# OpenMyxa.net
KiCad netlist of a schematic drawn in EAGLE
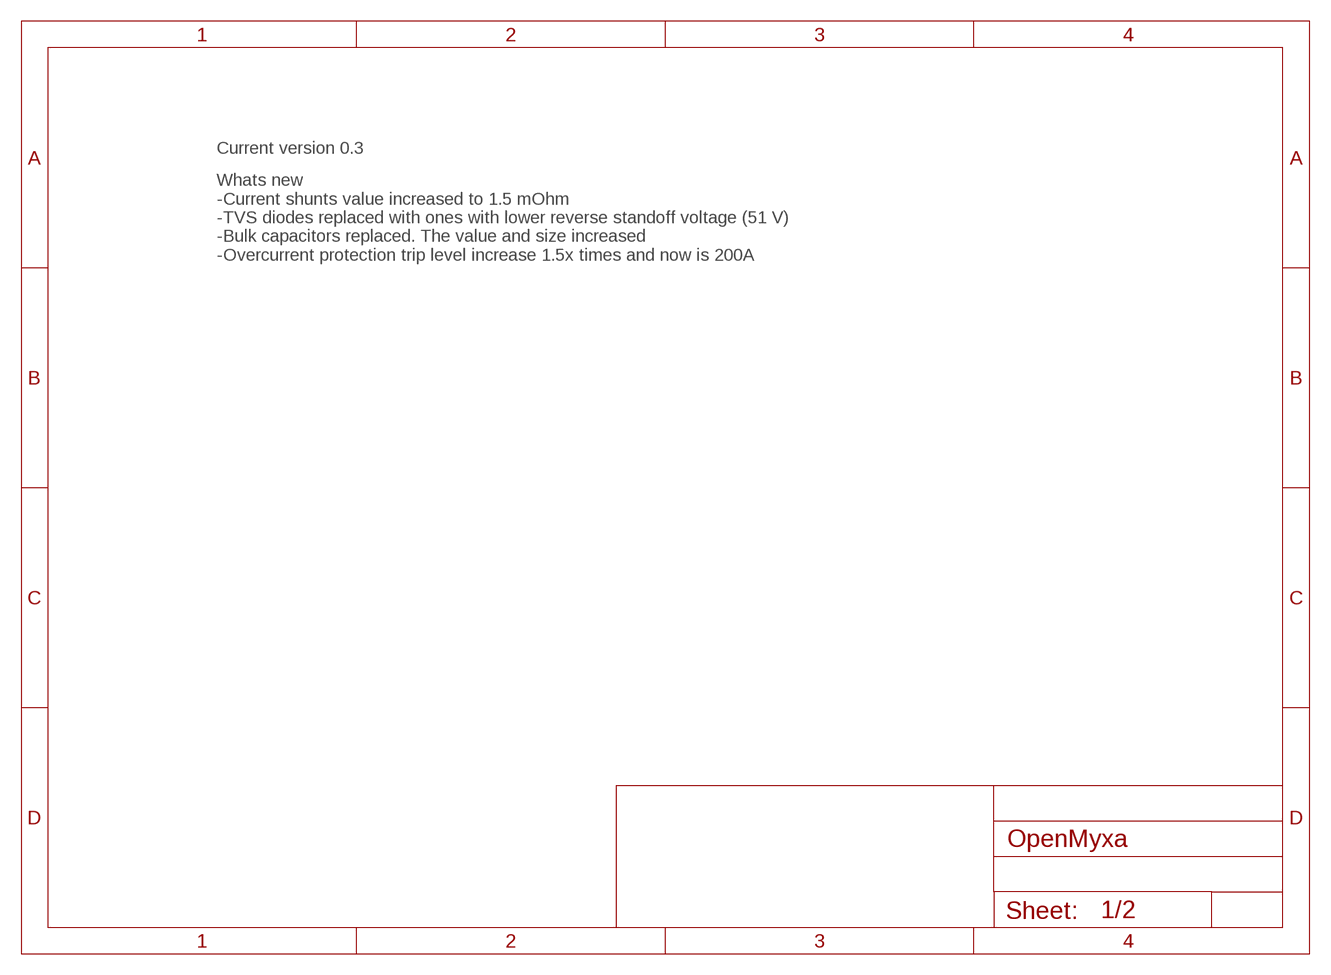
[diagram p0: schematic, sheet 1]
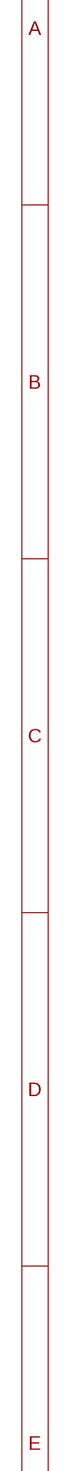
[diagram p1: schematic, sheet 2, part 1 of 2]
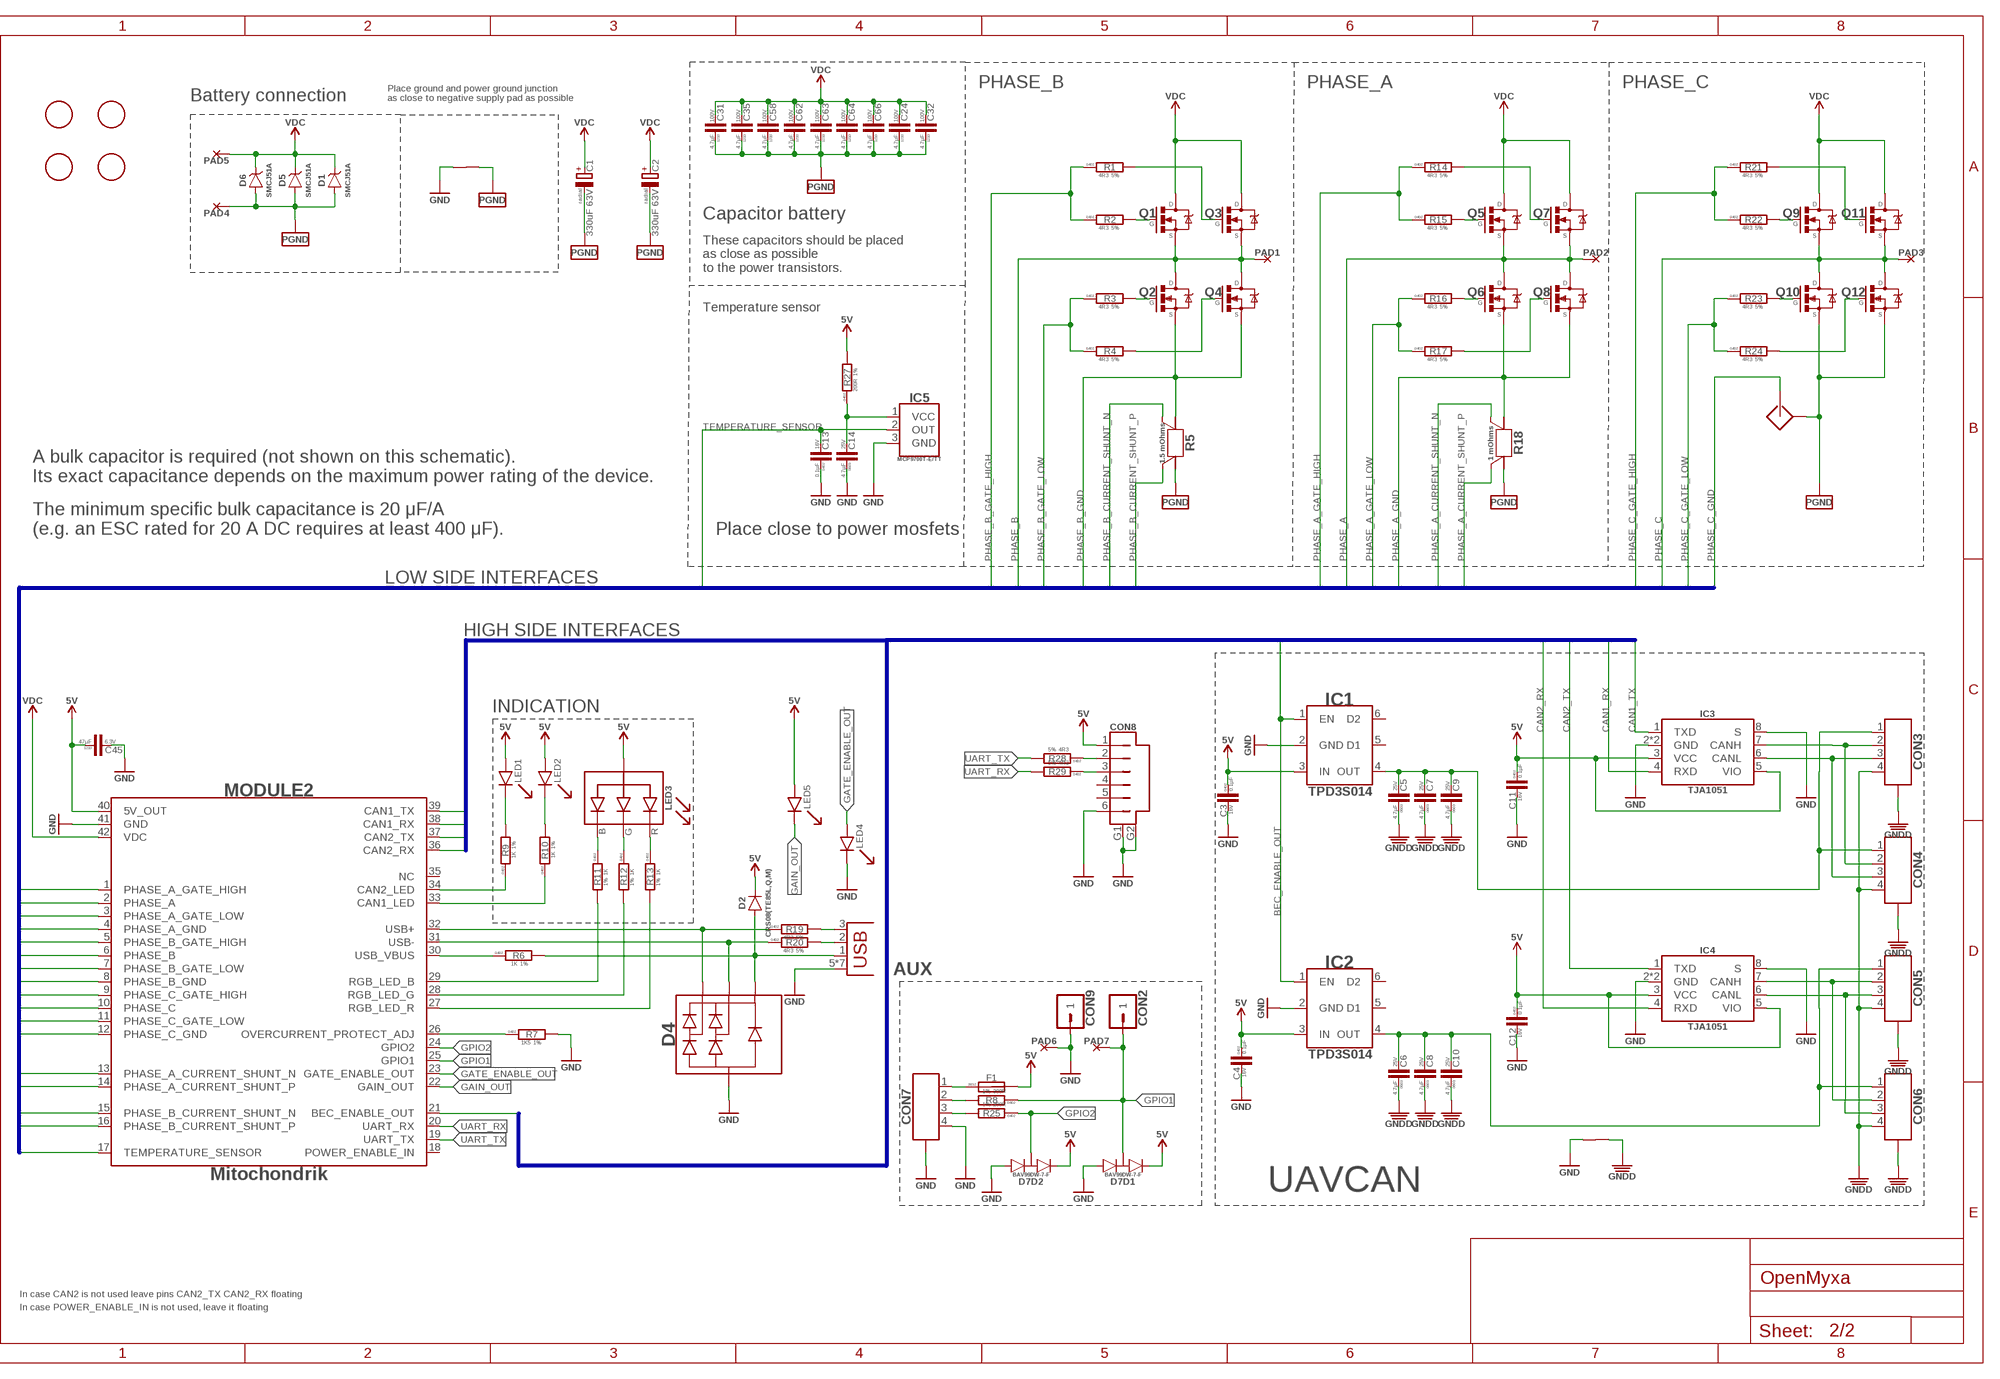
[diagram p2: schematic, sheet 2, part 2 of 2]

(export (version "E")
  (design (tool "Eeschema 10.0.6"))
  (components
    (comp (ref "C1")
      (value "330uF 63V")
      (footprint "eagle-import:SIDE_10X22")
      (fields
        (field (name "PACKAGE") "radial")
        (field (name "MANF") "EPCOS (TDK)")
        (field (name "DIGIKEY#") "565-2043-ND")
        (field (name "MANF_1") "United Chemi-Con")
        (field (name "MANF#") "ELXZ630ELL331MK20S")
      )
      (libsource (lib "eagle-import") (part "CPOL-SIDE"))
    )
    (comp (ref "C2")
      (value "330uF 63V")
      (footprint "eagle-import:SIDE_10X22")
      (fields
        (field (name "PACKAGE") "radial")
        (field (name "MANF") "EPCOS (TDK)")
        (field (name "DIGIKEY#") "565-2043-ND")
        (field (name "MANF_1") "United Chemi-Con")
        (field (name "MANF#") "ELXZ630ELL331MK20S")
      )
      (libsource (lib "eagle-import") (part "CPOL-SIDE"))
    )
    (comp (ref "C3")
      (value "0.1µF")
      (footprint "eagle-import:C0402")
      (fields
        (field (name "MANF") "Murata Electronics North America")
        (field (name "PACKAGE") "0402")
        (field (name "TOLERANCE") "+-10%")
        (field (name "VOLTAGE") "16V")
      )
      (libsource (lib "eagle-import") (part "0.1µF-0402-16V_10%_X7R"))
    )
    (comp (ref "C4")
      (value "0.1µF")
      (footprint "eagle-import:C0402")
      (fields
        (field (name "MANF") "Murata Electronics North America")
        (field (name "PACKAGE") "0402")
        (field (name "TOLERANCE") "+-10%")
        (field (name "VOLTAGE") "16V")
      )
      (libsource (lib "eagle-import") (part "0.1µF-0402-16V_10%_X7R"))
    )
    (comp (ref "C5")
      (value "4.7µF")
      (footprint "eagle-import:C0603")
      (fields
        (field (name "MANF") "Murata Electronics North America")
        (field (name "PACKAGE") "0603")
        (field (name "TOLERANCE") "+-10%")
        (field (name "VOLTAGE") "25V")
      )
      (libsource (lib "eagle-import") (part "4.7µF-0603-25V_10%_X6S"))
    )
    (comp (ref "C6")
      (value "4.7µF")
      (footprint "eagle-import:C0603")
      (fields
        (field (name "MANF") "Murata Electronics North America")
        (field (name "PACKAGE") "0603")
        (field (name "TOLERANCE") "+-10%")
        (field (name "VOLTAGE") "25V")
      )
      (libsource (lib "eagle-import") (part "4.7µF-0603-25V_10%_X6S"))
    )
    (comp (ref "C7")
      (value "4.7µF")
      (footprint "eagle-import:C0603")
      (fields
        (field (name "MANF") "Murata Electronics North America")
        (field (name "PACKAGE") "0603")
        (field (name "TOLERANCE") "+-10%")
        (field (name "VOLTAGE") "25V")
      )
      (libsource (lib "eagle-import") (part "4.7µF-0603-25V_10%_X6S"))
    )
    (comp (ref "C8")
      (value "4.7µF")
      (footprint "eagle-import:C0603")
      (fields
        (field (name "MANF") "Murata Electronics North America")
        (field (name "PACKAGE") "0603")
        (field (name "TOLERANCE") "+-10%")
        (field (name "VOLTAGE") "25V")
      )
      (libsource (lib "eagle-import") (part "4.7µF-0603-25V_10%_X6S"))
    )
    (comp (ref "C9")
      (value "4.7µF")
      (footprint "eagle-import:C0603")
      (fields
        (field (name "MANF") "Murata Electronics North America")
        (field (name "PACKAGE") "0603")
        (field (name "TOLERANCE") "+-10%")
        (field (name "VOLTAGE") "25V")
      )
      (libsource (lib "eagle-import") (part "4.7µF-0603-25V_10%_X6S"))
    )
    (comp (ref "C10")
      (value "4.7µF")
      (footprint "eagle-import:C0603")
      (fields
        (field (name "MANF") "Murata Electronics North America")
        (field (name "PACKAGE") "0603")
        (field (name "TOLERANCE") "+-10%")
        (field (name "VOLTAGE") "25V")
      )
      (libsource (lib "eagle-import") (part "4.7µF-0603-25V_10%_X6S"))
    )
    (comp (ref "C11")
      (value "0.1µF")
      (footprint "eagle-import:C0402")
      (fields
        (field (name "MANF") "Murata Electronics North America")
        (field (name "PACKAGE") "0402")
        (field (name "TOLERANCE") "+-10%")
        (field (name "VOLTAGE") "16V")
      )
      (libsource (lib "eagle-import") (part "0.1µF-0402-16V_10%_X7R"))
    )
    (comp (ref "C12")
      (value "0.1µF")
      (footprint "eagle-import:C0402")
      (fields
        (field (name "MANF") "Murata Electronics North America")
        (field (name "PACKAGE") "0402")
        (field (name "TOLERANCE") "+-10%")
        (field (name "VOLTAGE") "16V")
      )
      (libsource (lib "eagle-import") (part "0.1µF-0402-16V_10%_X7R"))
    )
    (comp (ref "C13")
      (value "0.1µF")
      (footprint "eagle-import:C0402")
      (fields
        (field (name "MANF") "Murata Electronics North America")
        (field (name "PACKAGE") "0402")
        (field (name "TOLERANCE") "+-10%")
        (field (name "VOLTAGE") "16V")
      )
      (libsource (lib "eagle-import") (part "0.1µF-0402-16V_10%_X7R"))
    )
    (comp (ref "C14")
      (value "4.7µF")
      (footprint "eagle-import:C0603")
      (fields
        (field (name "MANF") "Murata Electronics North America")
        (field (name "PACKAGE") "0603")
        (field (name "TOLERANCE") "+-10%")
        (field (name "VOLTAGE") "25V")
      )
      (libsource (lib "eagle-import") (part "4.7µF-0603-25V_10%_X6S"))
    )
    (comp (ref "C24")
      (value "4.7µF")
      (footprint "eagle-import:C1210")
      (fields
        (field (name "MANF") "TDK Corporation")
        (field (name "PACKAGE") "1210")
        (field (name "TOLERANCE") "+-20%")
        (field (name "VOLTAGE") "100V")
      )
      (libsource (lib "eagle-import") (part "myxa_masterlib_1040030_4.7µF-1210-100V_20%_X7S"))
    )
    (comp (ref "C31")
      (value "4.7µF")
      (footprint "eagle-import:C1210")
      (fields
        (field (name "MANF") "TDK Corporation")
        (field (name "PACKAGE") "1210")
        (field (name "TOLERANCE") "+-20%")
        (field (name "VOLTAGE") "100V")
      )
      (libsource (lib "eagle-import") (part "myxa_masterlib_1040030_4.7µF-1210-100V_20%_X7S"))
    )
    (comp (ref "C32")
      (value "4.7µF")
      (footprint "eagle-import:C1210")
      (fields
        (field (name "MANF") "TDK Corporation")
        (field (name "PACKAGE") "1210")
        (field (name "TOLERANCE") "+-20%")
        (field (name "VOLTAGE") "100V")
      )
      (libsource (lib "eagle-import") (part "myxa_masterlib_1040030_4.7µF-1210-100V_20%_X7S"))
    )
    (comp (ref "C35")
      (value "4.7µF")
      (footprint "eagle-import:C1210")
      (fields
        (field (name "MANF") "TDK Corporation")
        (field (name "PACKAGE") "1210")
        (field (name "TOLERANCE") "+-20%")
        (field (name "VOLTAGE") "100V")
      )
      (libsource (lib "eagle-import") (part "myxa_masterlib_1040030_4.7µF-1210-100V_20%_X7S"))
    )
    (comp (ref "C45")
      (value "47µF")
      (footprint "eagle-import:C1210")
      (fields
        (field (name "MANF") "TDK Corporation")
        (field (name "PACKAGE") "1210")
        (field (name "TOLERANCE") "+-20%")
        (field (name "VOLTAGE") "6.3V")
      )
      (libsource (lib "eagle-import") (part "47µF-1210-6.3V-20%-X7S"))
    )
    (comp (ref "C58")
      (value "4.7µF")
      (footprint "eagle-import:C1210")
      (fields
        (field (name "MANF") "TDK Corporation")
        (field (name "PACKAGE") "1210")
        (field (name "TOLERANCE") "+-20%")
        (field (name "VOLTAGE") "100V")
      )
      (libsource (lib "eagle-import") (part "myxa_masterlib_1040030_4.7µF-1210-100V_20%_X7S"))
    )
    (comp (ref "C62")
      (value "4.7µF")
      (footprint "eagle-import:C1210")
      (fields
        (field (name "MANF") "TDK Corporation")
        (field (name "PACKAGE") "1210")
        (field (name "TOLERANCE") "+-20%")
        (field (name "VOLTAGE") "100V")
      )
      (libsource (lib "eagle-import") (part "myxa_masterlib_1040030_4.7µF-1210-100V_20%_X7S"))
    )
    (comp (ref "C63")
      (value "4.7µF")
      (footprint "eagle-import:C1210")
      (fields
        (field (name "MANF") "TDK Corporation")
        (field (name "PACKAGE") "1210")
        (field (name "TOLERANCE") "+-20%")
        (field (name "VOLTAGE") "100V")
      )
      (libsource (lib "eagle-import") (part "myxa_masterlib_1040030_4.7µF-1210-100V_20%_X7S"))
    )
    (comp (ref "C64")
      (value "4.7µF")
      (footprint "eagle-import:C1210")
      (fields
        (field (name "MANF") "TDK Corporation")
        (field (name "PACKAGE") "1210")
        (field (name "TOLERANCE") "+-20%")
        (field (name "VOLTAGE") "100V")
      )
      (libsource (lib "eagle-import") (part "myxa_masterlib_1040030_4.7µF-1210-100V_20%_X7S"))
    )
    (comp (ref "C66")
      (value "4.7µF")
      (footprint "eagle-import:C1210")
      (fields
        (field (name "MANF") "TDK Corporation")
        (field (name "PACKAGE") "1210")
        (field (name "TOLERANCE") "+-20%")
        (field (name "VOLTAGE") "100V")
      )
      (libsource (lib "eagle-import") (part "myxa_masterlib_1040030_4.7µF-1210-100V_20%_X7S"))
    )
    (comp (ref "CON1")
      (value "USB")
      (footprint "eagle-import:1051330011")
      (fields (field (name "MANF") "Molex LLC"))
      (libsource (lib "eagle-import") (part "USB"))
    )
    (comp (ref "CON2")
      (value "PINHEAD_1X01-2")
      (footprint "eagle-import:1X01-PTH-2")
      (libsource (lib "eagle-import") (part "PINHEAD_1X01-2"))
    )
    (comp (ref "CON3")
      (value "CON-4P-TABS-STRAIGHT")
      (footprint "eagle-import:JST_GH-4P-STRAIGHT")
      (fields (field (name "MANF") "JST Sales America Inc"))
      (libsource (lib "eagle-import") (part "CON-4P-TABS-STRAIGHT"))
    )
    (comp (ref "CON4")
      (value "CON-4P-TABS-STRAIGHT")
      (footprint "eagle-import:JST_GH-4P-STRAIGHT")
      (fields (field (name "MANF") "JST Sales America Inc"))
      (libsource (lib "eagle-import") (part "CON-4P-TABS-STRAIGHT"))
    )
    (comp (ref "CON5")
      (value "CON-4P-TABS-STRAIGHT")
      (footprint "eagle-import:JST_GH-4P-STRAIGHT")
      (fields (field (name "MANF") "JST Sales America Inc"))
      (libsource (lib "eagle-import") (part "CON-4P-TABS-STRAIGHT"))
    )
    (comp (ref "CON6")
      (value "CON-4P-TABS-STRAIGHT")
      (footprint "eagle-import:JST_GH-4P-STRAIGHT")
      (fields (field (name "MANF") "JST Sales America Inc"))
      (libsource (lib "eagle-import") (part "CON-4P-TABS-STRAIGHT"))
    )
    (comp (ref "CON7")
      (value "CON-4P-TABS-STRAIGHT")
      (footprint "eagle-import:JST_GH-4P-STRAIGHT")
      (fields (field (name "MANF") "JST Sales America Inc"))
      (libsource (lib "eagle-import") (part "CON-4P-TABS-STRAIGHT"))
    )
    (comp (ref "CON8")
      (value "CON-6P")
      (footprint "eagle-import:SM06B")
      (fields (field (name "MANF") "JST Sales America Inc"))
      (libsource (lib "eagle-import") (part "CON-6P"))
    )
    (comp (ref "CON9")
      (value "PINHEAD_1X01-2")
      (footprint "eagle-import:1X01-PTH-2")
      (libsource (lib "eagle-import") (part "PINHEAD_1X01-2"))
    )
    (comp (ref "D1")
      (value "SMCJ51A")
      (footprint "eagle-import:DO-214AB(SMC)")
      (fields (field (name "MANF#") "SMCJ51A") (field (name "MANF") "Littelfuse Inc."))
      (libsource (lib "eagle-import") (part "SMCJ51A"))
    )
    (comp (ref "D2")
      (value "CRS08-SOD123")
      (footprint "eagle-import:SOD123")
      (fields
        (field (name "MANF#") "CRS08(TE85L,Q,M)")
        (field (name "MANF") "Toshiba Semiconductor and Storage")
      )
      (libsource (lib "eagle-import") (part "CRS08-SOD123"))
    )
    (comp (ref "D4")
      (value "PRTR5V0U2X")
      (footprint "eagle-import:SOT143B")
      (fields (field (name "MANF") "NXP USA Inc"))
      (libsource (lib "eagle-import") (part "PRTR5V0U2X"))
    )
    (comp (ref "D5")
      (value "SMCJ51A")
      (footprint "eagle-import:DO-214AB(SMC)")
      (fields (field (name "MANF#") "SMCJ51A") (field (name "MANF") "Littelfuse Inc."))
      (libsource (lib "eagle-import") (part "SMCJ51A"))
    )
    (comp (ref "D6")
      (value "SMCJ51A")
      (footprint "eagle-import:DO-214AB(SMC)")
      (fields (field (name "MANF#") "SMCJ51A") (field (name "MANF") "Littelfuse Inc."))
      (libsource (lib "eagle-import") (part "SMCJ51A"))
    )
    (comp (ref "D7")
      (value "BAV99DW")
      (footprint "eagle-import:SOT363")
      (fields (field (name "MANF#") "BAV99DW-7-F") (field (name "MANF") "Diodes Incorporated"))
      (libsource (lib "eagle-import") (part "BAV99DW"))
    )
    (comp (ref "F1")
      (value "FUSE-1812")
      (footprint "eagle-import:F1812")
      (fields (field (name "PACKAGE") "1812") (field (name "MANF") "Bel Fuse Inc"))
      (libsource (lib "eagle-import") (part "FUSE-1812"))
    )
    (comp (ref "IC1")
      (value "TPD3S014DBVR-SOT23-6")
      (footprint "eagle-import:SOT26")
      (fields (field (name "MANF") "Texas Instruments"))
      (libsource (lib "eagle-import") (part "TPD3S014DBVR-SOT23-6"))
    )
    (comp (ref "IC2")
      (value "TPD3S014DBVR-SOT23-6")
      (footprint "eagle-import:SOT26")
      (fields (field (name "MANF") "Texas Instruments"))
      (libsource (lib "eagle-import") (part "TPD3S014DBVR-SOT23-6"))
    )
    (comp (ref "IC3")
      (value "TJA1051")
      (footprint "eagle-import:SOT782-1")
      (fields (field (name "MANF") "NXP Semiconductors"))
      (libsource (lib "eagle-import") (part "TJA1051"))
    )
    (comp (ref "IC4")
      (value "TJA1051")
      (footprint "eagle-import:SOT782-1")
      (fields (field (name "MANF") "NXP Semiconductors"))
      (libsource (lib "eagle-import") (part "TJA1051"))
    )
    (comp (ref "IC5")
      (value "MCP9700")
      (footprint "eagle-import:SOT23B-3")
      (fields (field (name "MANF#") "MCP9700T-E/TT") (field (name "MANF") "Microchip Technology"))
      (libsource (lib "eagle-import") (part "MCP9700"))
    )
    (comp (ref "LED1")
      (value "GREEN")
      (footprint "eagle-import:0402_LED")
      (fields (field (name "MANF") "Rohm Semiconductor"))
      (libsource (lib "eagle-import") (part "LED-0402-GREEN"))
    )
    (comp (ref "LED2")
      (value "GREEN")
      (footprint "eagle-import:0402_LED")
      (fields (field (name "MANF") "Rohm Semiconductor"))
      (libsource (lib "eagle-import") (part "LED-0402-GREEN"))
    )
    (comp (ref "LED3")
      (value "LTST-C19HE1WT")
      (footprint "eagle-import:LITE_ON_RGB_LED")
      (fields (field (name "MANF") "Lite-On Inc"))
      (libsource (lib "eagle-import") (part "LTST-C19HE1WT"))
    )
    (comp (ref "LED4")
      (value "ORANGE")
      (footprint "eagle-import:0402_LED")
      (fields (field (name "MANF") "Rohm Semiconductor"))
      (libsource (lib "eagle-import") (part "LED-0402-ORANGE"))
    )
    (comp (ref "LED5")
      (value "ORANGE")
      (footprint "eagle-import:0402_LED")
      (fields (field (name "MANF") "Rohm Semiconductor"))
      (libsource (lib "eagle-import") (part "LED-0402-ORANGE"))
    )
    (comp (ref "MODULE2")
      (value "MITOHONDRIQUE_V0.2-TH")
      (footprint "eagle-import:MITOHONDRIQUE-TH")
      (fields (field (name "MANF#") "Mitochondrik") (field (name "MANF") "Zubax Robotics"))
      (libsource (lib "eagle-import") (part "MITOHONDRIQUE_V0.2-TH"))
    )
    (comp (ref "PAD1")
      (value "PAD-HOLE_2")
      (footprint "eagle-import:HOLE_2")
      (libsource (lib "eagle-import") (part "PAD-HOLE_2"))
    )
    (comp (ref "PAD2")
      (value "PAD-HOLE_2")
      (footprint "eagle-import:HOLE_2")
      (libsource (lib "eagle-import") (part "PAD-HOLE_2"))
    )
    (comp (ref "PAD3")
      (value "PAD-HOLE_2")
      (footprint "eagle-import:HOLE_2")
      (libsource (lib "eagle-import") (part "PAD-HOLE_2"))
    )
    (comp (ref "PAD4")
      (value "PAD-HOLE_2.5")
      (footprint "eagle-import:HOLE_2.5")
      (libsource (lib "eagle-import") (part "PAD-HOLE_2.5"))
    )
    (comp (ref "PAD5")
      (value "PAD-HOLE_2.5")
      (footprint "eagle-import:HOLE_2.5")
      (libsource (lib "eagle-import") (part "PAD-HOLE_2.5"))
    )
    (comp (ref "PAD6")
      (value "PAD-3X1.5")
      (footprint "eagle-import:3X1.5")
      (libsource (lib "eagle-import") (part "PAD-3X1.5"))
    )
    (comp (ref "PAD7")
      (value "PAD-3X1.5")
      (footprint "eagle-import:3X1.5")
      (libsource (lib "eagle-import") (part "PAD-3X1.5"))
    )
    (comp (ref "Q1")
      (value "BSC040N08NS5ATMA1-PG-TDSON-8-7")
      (footprint "eagle-import:PG-TDSON-8-7")
      (fields (field (name "MANF") "Infineon Technologies"))
      (libsource (lib "eagle-import") (part "BSC040N08NS5ATMA1-PG-TDSON-8-7"))
    )
    (comp (ref "Q2")
      (value "BSC040N08NS5ATMA1-PG-TDSON-8-7")
      (footprint "eagle-import:PG-TDSON-8-7")
      (fields (field (name "MANF") "Infineon Technologies"))
      (libsource (lib "eagle-import") (part "BSC040N08NS5ATMA1-PG-TDSON-8-7"))
    )
    (comp (ref "Q3")
      (value "BSC040N08NS5ATMA1-PG-TDSON-8-7")
      (footprint "eagle-import:PG-TDSON-8-7")
      (fields (field (name "MANF") "Infineon Technologies"))
      (libsource (lib "eagle-import") (part "BSC040N08NS5ATMA1-PG-TDSON-8-7"))
    )
    (comp (ref "Q4")
      (value "BSC040N08NS5ATMA1-PG-TDSON-8-7")
      (footprint "eagle-import:PG-TDSON-8-7")
      (fields (field (name "MANF") "Infineon Technologies"))
      (libsource (lib "eagle-import") (part "BSC040N08NS5ATMA1-PG-TDSON-8-7"))
    )
    (comp (ref "Q5")
      (value "BSC040N08NS5ATMA1-PG-TDSON-8-7")
      (footprint "eagle-import:PG-TDSON-8-7")
      (fields (field (name "MANF") "Infineon Technologies"))
      (libsource (lib "eagle-import") (part "BSC040N08NS5ATMA1-PG-TDSON-8-7"))
    )
    (comp (ref "Q6")
      (value "BSC040N08NS5ATMA1-PG-TDSON-8-7")
      (footprint "eagle-import:PG-TDSON-8-7")
      (fields (field (name "MANF") "Infineon Technologies"))
      (libsource (lib "eagle-import") (part "BSC040N08NS5ATMA1-PG-TDSON-8-7"))
    )
    (comp (ref "Q7")
      (value "BSC040N08NS5ATMA1-PG-TDSON-8-7")
      (footprint "eagle-import:PG-TDSON-8-7")
      (fields (field (name "MANF") "Infineon Technologies"))
      (libsource (lib "eagle-import") (part "BSC040N08NS5ATMA1-PG-TDSON-8-7"))
    )
    (comp (ref "Q8")
      (value "BSC040N08NS5ATMA1-PG-TDSON-8-7")
      (footprint "eagle-import:PG-TDSON-8-7")
      (fields (field (name "MANF") "Infineon Technologies"))
      (libsource (lib "eagle-import") (part "BSC040N08NS5ATMA1-PG-TDSON-8-7"))
    )
    (comp (ref "Q9")
      (value "BSC040N08NS5ATMA1-PG-TDSON-8-7")
      (footprint "eagle-import:PG-TDSON-8-7")
      (fields (field (name "MANF") "Infineon Technologies"))
      (libsource (lib "eagle-import") (part "BSC040N08NS5ATMA1-PG-TDSON-8-7"))
    )
    (comp (ref "Q10")
      (value "BSC040N08NS5ATMA1-PG-TDSON-8-7")
      (footprint "eagle-import:PG-TDSON-8-7")
      (fields (field (name "MANF") "Infineon Technologies"))
      (libsource (lib "eagle-import") (part "BSC040N08NS5ATMA1-PG-TDSON-8-7"))
    )
    (comp (ref "Q11")
      (value "BSC040N08NS5ATMA1-PG-TDSON-8-7")
      (footprint "eagle-import:PG-TDSON-8-7")
      (fields (field (name "MANF") "Infineon Technologies"))
      (libsource (lib "eagle-import") (part "BSC040N08NS5ATMA1-PG-TDSON-8-7"))
    )
    (comp (ref "Q12")
      (value "BSC040N08NS5ATMA1-PG-TDSON-8-7")
      (footprint "eagle-import:PG-TDSON-8-7")
      (fields (field (name "MANF") "Infineon Technologies"))
      (libsource (lib "eagle-import") (part "BSC040N08NS5ATMA1-PG-TDSON-8-7"))
    )
    (comp (ref "R1")
      (value "4R3")
      (footprint "eagle-import:R0402")
      (fields (field (name "MANF") "Yageo") (field (name "PACKAGE") "0402") (field (name "TOLERANCE") "5%"))
      (libsource (lib "eagle-import") (part "4R3-0402-5%"))
    )
    (comp (ref "R2")
      (value "4R3")
      (footprint "eagle-import:R0402")
      (fields (field (name "MANF") "Yageo") (field (name "PACKAGE") "0402") (field (name "TOLERANCE") "5%"))
      (libsource (lib "eagle-import") (part "4R3-0402-5%"))
    )
    (comp (ref "R3")
      (value "4R3")
      (footprint "eagle-import:R0402")
      (fields (field (name "MANF") "Yageo") (field (name "PACKAGE") "0402") (field (name "TOLERANCE") "5%"))
      (libsource (lib "eagle-import") (part "4R3-0402-5%"))
    )
    (comp (ref "R4")
      (value "4R3")
      (footprint "eagle-import:R0402")
      (fields (field (name "MANF") "Yageo") (field (name "PACKAGE") "0402") (field (name "TOLERANCE") "5%"))
      (libsource (lib "eagle-import") (part "4R3-0402-5%"))
    )
    (comp (ref "R5")
      (value "1.5 mOhms")
      (footprint "eagle-import:R2512-KELVIN")
      (fields
        (field (name "MANF") "Stackpole Electronics Inc.")
        (field (name "POWER") "2W")
        (field (name "TOLERANCE") "±1%")
        (field (name "DIGIKEY#") "696-1184-1-ND")
        (field (name "MANF_1") "Riedon")
        (field (name "MANF#") "CSR2512C0R0015F")
        (field (name "POWER_1") "3W")
      )
      (libsource (lib "eagle-import") (part "CURRENT_SHUNT_KELVIN-2512-KELVIN-0.001R"))
    )
    (comp (ref "R6")
      (value "1K")
      (footprint "eagle-import:R0402")
      (fields (field (name "MANF") "Yageo") (field (name "PACKAGE") "0402") (field (name "TOLERANCE") "1%"))
      (libsource (lib "eagle-import") (part "1K-0402-1%"))
    )
    (comp (ref "R7")
      (value "1K5")
      (footprint "eagle-import:R0402")
      (fields
        (field (name "PACKAGE") "0402")
        (field (name "TOLERANCE") "1%")
        (field (name "AEC-Q") "AEC-Q200")
        (field (name "DIGIKEY#") "P1.50KLCT-ND")
        (field (name "MANF") "Panasonic Electronic Components")
        (field (name "MANF#") "ERJ-2RKF1501X")
      )
      (libsource (lib "eagle-import") (part "R-0402-1%"))
    )
    (comp (ref "R8")
      (value "200R")
      (footprint "eagle-import:R0402")
      (fields (field (name "MANF") "Yageo") (field (name "PACKAGE") "0402") (field (name "TOLERANCE") "1%"))
      (libsource (lib "eagle-import") (part "200R-0402-1%"))
    )
    (comp (ref "R9")
      (value "1K")
      (footprint "eagle-import:R0402")
      (fields (field (name "MANF") "Yageo") (field (name "PACKAGE") "0402") (field (name "TOLERANCE") "1%"))
      (libsource (lib "eagle-import") (part "1K-0402-1%"))
    )
    (comp (ref "R10")
      (value "1K")
      (footprint "eagle-import:R0402")
      (fields (field (name "MANF") "Yageo") (field (name "PACKAGE") "0402") (field (name "TOLERANCE") "1%"))
      (libsource (lib "eagle-import") (part "1K-0402-1%"))
    )
    (comp (ref "R11")
      (value "1K")
      (footprint "eagle-import:R0402")
      (fields (field (name "MANF") "Yageo") (field (name "PACKAGE") "0402") (field (name "TOLERANCE") "1%"))
      (libsource (lib "eagle-import") (part "1K-0402-1%"))
    )
    (comp (ref "R12")
      (value "1K")
      (footprint "eagle-import:R0402")
      (fields (field (name "MANF") "Yageo") (field (name "PACKAGE") "0402") (field (name "TOLERANCE") "1%"))
      (libsource (lib "eagle-import") (part "1K-0402-1%"))
    )
    (comp (ref "R13")
      (value "1K")
      (footprint "eagle-import:R0402")
      (fields (field (name "MANF") "Yageo") (field (name "PACKAGE") "0402") (field (name "TOLERANCE") "1%"))
      (libsource (lib "eagle-import") (part "1K-0402-1%"))
    )
    (comp (ref "R14")
      (value "4R3")
      (footprint "eagle-import:R0402")
      (fields (field (name "MANF") "Yageo") (field (name "PACKAGE") "0402") (field (name "TOLERANCE") "5%"))
      (libsource (lib "eagle-import") (part "4R3-0402-5%"))
    )
    (comp (ref "R15")
      (value "4R3")
      (footprint "eagle-import:R0402")
      (fields (field (name "MANF") "Yageo") (field (name "PACKAGE") "0402") (field (name "TOLERANCE") "5%"))
      (libsource (lib "eagle-import") (part "4R3-0402-5%"))
    )
    (comp (ref "R16")
      (value "4R3")
      (footprint "eagle-import:R0402")
      (fields (field (name "MANF") "Yageo") (field (name "PACKAGE") "0402") (field (name "TOLERANCE") "5%"))
      (libsource (lib "eagle-import") (part "4R3-0402-5%"))
    )
    (comp (ref "R17")
      (value "4R3")
      (footprint "eagle-import:R0402")
      (fields (field (name "MANF") "Yageo") (field (name "PACKAGE") "0402") (field (name "TOLERANCE") "5%"))
      (libsource (lib "eagle-import") (part "4R3-0402-5%"))
    )
    (comp (ref "R18")
      (value "1 mOhms")
      (footprint "eagle-import:R2512-KELVIN")
      (fields
        (field (name "MANF") "Stackpole Electronics Inc.")
        (field (name "POWER") "2W")
        (field (name "TOLERANCE") "±1%")
        (field (name "DIGIKEY#") "696-1184-1-ND")
        (field (name "MANF_1") "Riedon")
        (field (name "MANF#") "CSR2512C0R0015F")
        (field (name "POWER_1") "3W")
      )
      (libsource (lib "eagle-import") (part "CURRENT_SHUNT_KELVIN-2512-KELVIN-0.001R"))
    )
    (comp (ref "R19")
      (value "4R3")
      (footprint "eagle-import:R0402")
      (fields (field (name "MANF") "Yageo") (field (name "PACKAGE") "0402") (field (name "TOLERANCE") "5%"))
      (libsource (lib "eagle-import") (part "4R3-0402-5%"))
    )
    (comp (ref "R20")
      (value "4R3")
      (footprint "eagle-import:R0402")
      (fields (field (name "MANF") "Yageo") (field (name "PACKAGE") "0402") (field (name "TOLERANCE") "5%"))
      (libsource (lib "eagle-import") (part "4R3-0402-5%"))
    )
    (comp (ref "R21")
      (value "4R3")
      (footprint "eagle-import:R0402")
      (fields (field (name "MANF") "Yageo") (field (name "PACKAGE") "0402") (field (name "TOLERANCE") "5%"))
      (libsource (lib "eagle-import") (part "4R3-0402-5%"))
    )
    (comp (ref "R22")
      (value "4R3")
      (footprint "eagle-import:R0402")
      (fields (field (name "MANF") "Yageo") (field (name "PACKAGE") "0402") (field (name "TOLERANCE") "5%"))
      (libsource (lib "eagle-import") (part "4R3-0402-5%"))
    )
    (comp (ref "R23")
      (value "4R3")
      (footprint "eagle-import:R0402")
      (fields (field (name "MANF") "Yageo") (field (name "PACKAGE") "0402") (field (name "TOLERANCE") "5%"))
      (libsource (lib "eagle-import") (part "4R3-0402-5%"))
    )
    (comp (ref "R24")
      (value "4R3")
      (footprint "eagle-import:R0402")
      (fields (field (name "MANF") "Yageo") (field (name "PACKAGE") "0402") (field (name "TOLERANCE") "5%"))
      (libsource (lib "eagle-import") (part "4R3-0402-5%"))
    )
    (comp (ref "R25")
      (value "200R")
      (footprint "eagle-import:R0402")
      (fields (field (name "MANF") "Yageo") (field (name "PACKAGE") "0402") (field (name "TOLERANCE") "1%"))
      (libsource (lib "eagle-import") (part "200R-0402-1%"))
    )
    (comp (ref "R27")
      (value "200R")
      (footprint "eagle-import:R0402")
      (fields (field (name "MANF") "Yageo") (field (name "PACKAGE") "0402") (field (name "TOLERANCE") "1%"))
      (libsource (lib "eagle-import") (part "200R-0402-1%"))
    )
    (comp (ref "R28")
      (value "4R3")
      (footprint "eagle-import:R0402")
      (fields (field (name "MANF") "Yageo") (field (name "PACKAGE") "0402") (field (name "TOLERANCE") "5%"))
      (libsource (lib "eagle-import") (part "4R3-0402-5%"))
    )
    (comp (ref "R29")
      (value "4R3")
      (footprint "eagle-import:R0402")
      (fields (field (name "MANF") "Yageo") (field (name "PACKAGE") "0402") (field (name "TOLERANCE") "5%"))
      (libsource (lib "eagle-import") (part "4R3-0402-5%"))
    )
    (comp (ref "S1")
      (value "SENSE")
      (footprint "eagle-import:CURRENT_SHUNT_SENSE")
      (libsource (lib "eagle-import") (part "SENSE"))
    )
    (comp (ref "U$1")
      (value "CONNECTION")
      (footprint "eagle-import:CONNECTION")
      (libsource (lib "eagle-import") (part "CONNECTION"))
    )
    (comp (ref "U$3")
      (value "CONNECTION")
      (footprint "eagle-import:CONNECTION")
      (libsource (lib "eagle-import") (part "CONNECTION"))
    )
    (comp (ref "U$5")
      (value "FIDUCIALMOUNT")
      (footprint "eagle-import:FIDUCIA-MOUNT")
      (libsource (lib "eagle-import") (part "FIDUCIALMOUNT"))
    )
    (comp (ref "U$6")
      (value "FIDUCIALMOUNT")
      (footprint "eagle-import:FIDUCIA-MOUNT")
      (libsource (lib "eagle-import") (part "FIDUCIALMOUNT"))
    )
    (comp (ref "U$7")
      (value "FIDUCIALMOUNT")
      (footprint "eagle-import:FIDUCIA-MOUNT")
      (libsource (lib "eagle-import") (part "FIDUCIALMOUNT"))
    )
    (comp (ref "U$11")
      (value "FIDUCIALMOUNT")
      (footprint "eagle-import:FIDUCIA-MOUNT")
      (libsource (lib "eagle-import") (part "FIDUCIALMOUNT"))
    )
  )
  (nets
    (net (code "1") (name "BEC_ENABLE_OUT") (class "Default")
      (node (ref "IC1") (pin "1") (pinfunction "EN_1") (pintype "bidirectional"))
      (node (ref "IC2") (pin "1") (pinfunction "EN_1") (pintype "bidirectional"))
      (node (ref "MODULE2") (pin "21") (pinfunction "BEC_ENABLE_OUT_21") (pintype "output"))
    )
    (net (code "2") (name "CAN1_RX") (class "Default")
      (node (ref "IC3") (pin "4") (pinfunction "RXD_4") (pintype "bidirectional"))
      (node (ref "MODULE2") (pin "38") (pinfunction "CAN1_RX_38") (pintype "input"))
    )
    (net (code "3") (name "CAN1_TX") (class "Default")
      (node (ref "IC3") (pin "1") (pinfunction "TXD_1") (pintype "bidirectional"))
      (node (ref "MODULE2") (pin "39") (pinfunction "CAN1_TX_39") (pintype "output"))
    )
    (net (code "4") (name "CAN2_RX") (class "Default")
      (node (ref "IC4") (pin "4") (pinfunction "RXD_4") (pintype "bidirectional"))
      (node (ref "MODULE2") (pin "36") (pinfunction "CAN2_RX_36") (pintype "input"))
    )
    (net (code "5") (name "CAN2_TX") (class "Default")
      (node (ref "IC4") (pin "1") (pinfunction "TXD_1") (pintype "bidirectional"))
      (node (ref "MODULE2") (pin "37") (pinfunction "CAN2_TX_37") (pintype "output"))
    )
    (net (code "6") (name "GAIN_OUT") (class "Default")
      (node (ref "LED5") (pin "C") (pinfunction "C_C") (pintype "bidirectional"))
      (node (ref "MODULE2") (pin "22") (pinfunction "GAIN_OUT_22") (pintype "output"))
    )
    (net (code "7") (name "GATE_ENABLE_OUT") (class "Default")
      (node (ref "LED4") (pin "A") (pinfunction "A_A") (pintype "bidirectional"))
      (node (ref "MODULE2") (pin "23") (pinfunction "GATE_ENABLE_OUT_23") (pintype "output"))
    )
    (net (code "8") (name "GND") (class "Default")
      (node (ref "C11") (pin "2") (pinfunction "2_2") (pintype "passive"))
      (node (ref "C12") (pin "2") (pinfunction "2_2") (pintype "passive"))
      (node (ref "C13") (pin "1") (pinfunction "1_1") (pintype "passive"))
      (node (ref "C14") (pin "P$1") (pinfunction "1_P$1") (pintype "passive"))
      (node (ref "C3") (pin "2") (pinfunction "2_2") (pintype "passive"))
      (node (ref "C4") (pin "2") (pinfunction "2_2") (pintype "passive"))
      (node (ref "C45") (pin "2") (pinfunction "2_2") (pintype "passive"))
      (node (ref "CON1") (pin "5") (pinfunction "GND_5") (pintype "bidirectional"))
      (node (ref "CON1") (pin "P$1") (pinfunction "GND_P$1") (pintype "bidirectional"))
      (node (ref "CON1") (pin "P$2") (pinfunction "GND_P$2") (pintype "bidirectional"))
      (node (ref "CON1") (pin "P$3") (pinfunction "GND_P$3") (pintype "bidirectional"))
      (node (ref "CON1") (pin "P$4") (pinfunction "GND_P$4") (pintype "bidirectional"))
      (node (ref "CON1") (pin "P$5") (pinfunction "GND_P$5") (pintype "bidirectional"))
      (node (ref "CON1") (pin "P$6") (pinfunction "GND_P$6") (pintype "bidirectional"))
      (node (ref "CON7") (pin "4") (pinfunction "4_4") (pintype "bidirectional"))
      (node (ref "CON7") (pin "M$0") (pinfunction "GND_M$0") (pintype "bidirectional"))
      (node (ref "CON7") (pin "M$1") (pinfunction "GND_M$1") (pintype "bidirectional"))
      (node (ref "CON8") (pin "6") (pinfunction "6_6") (pintype "passive"))
      (node (ref "CON8") (pin "G1") (pinfunction "G1_G1") (pintype "passive"))
      (node (ref "CON8") (pin "G2") (pinfunction "G2_G2") (pintype "passive"))
      (node (ref "CON9") (pin "1") (pinfunction "1_1") (pintype "passive"))
      (node (ref "D4") (pin "1") (pinfunction "C_1") (pintype "bidirectional"))
      (node (ref "D7") (pin "1") (pinfunction "A_1") (pintype "passive"))
      (node (ref "D7") (pin "4") (pinfunction "A_4") (pintype "passive"))
      (node (ref "IC1") (pin "2") (pinfunction "GND_2") (pintype "bidirectional"))
      (node (ref "IC2") (pin "2") (pinfunction "GND_2") (pintype "bidirectional"))
      (node (ref "IC3") (pin "2") (pinfunction "GND_2") (pintype "bidirectional"))
      (node (ref "IC3") (pin "8") (pinfunction "S_8") (pintype "bidirectional"))
      (node (ref "IC3") (pin "PAD") (pinfunction "GND_PAD") (pintype "bidirectional"))
      (node (ref "IC4") (pin "2") (pinfunction "GND_2") (pintype "bidirectional"))
      (node (ref "IC4") (pin "8") (pinfunction "S_8") (pintype "bidirectional"))
      (node (ref "IC4") (pin "PAD") (pinfunction "GND_PAD") (pintype "bidirectional"))
      (node (ref "IC5") (pin "3") (pinfunction "GND_3") (pintype "bidirectional"))
      (node (ref "LED4") (pin "C") (pinfunction "C_C") (pintype "bidirectional"))
      (node (ref "MODULE2") (pin "41") (pinfunction "GND_41") (pintype "power_in"))
      (node (ref "PAD6") (pin "P$1") (pinfunction "P$1_P$1") (pintype "bidirectional"))
      (node (ref "R7") (pin "2") (pinfunction "2_2") (pintype "passive"))
      (node (ref "U$1") (pin "P$1") (pinfunction "P$1_P$1") (pintype "bidirectional"))
      (node (ref "U$3") (pin "P$1") (pinfunction "P$1_P$1") (pintype "bidirectional"))
    )
    (net (code "9") (name "GNDD") (class "Default")
      (node (ref "C10") (pin "P$1") (pinfunction "1_P$1") (pintype "passive"))
      (node (ref "C5") (pin "P$1") (pinfunction "1_P$1") (pintype "passive"))
      (node (ref "C6") (pin "P$1") (pinfunction "1_P$1") (pintype "passive"))
      (node (ref "C7") (pin "P$1") (pinfunction "1_P$1") (pintype "passive"))
      (node (ref "C8") (pin "P$1") (pinfunction "1_P$1") (pintype "passive"))
      (node (ref "C9") (pin "P$1") (pinfunction "1_P$1") (pintype "passive"))
      (node (ref "CON3") (pin "4") (pinfunction "4_4") (pintype "bidirectional"))
      (node (ref "CON3") (pin "M$0") (pinfunction "GND_M$0") (pintype "bidirectional"))
      (node (ref "CON3") (pin "M$1") (pinfunction "GND_M$1") (pintype "bidirectional"))
      (node (ref "CON4") (pin "4") (pinfunction "4_4") (pintype "bidirectional"))
      (node (ref "CON4") (pin "M$0") (pinfunction "GND_M$0") (pintype "bidirectional"))
      (node (ref "CON4") (pin "M$1") (pinfunction "GND_M$1") (pintype "bidirectional"))
      (node (ref "CON5") (pin "4") (pinfunction "4_4") (pintype "bidirectional"))
      (node (ref "CON5") (pin "M$0") (pinfunction "GND_M$0") (pintype "bidirectional"))
      (node (ref "CON5") (pin "M$1") (pinfunction "GND_M$1") (pintype "bidirectional"))
      (node (ref "CON6") (pin "4") (pinfunction "4_4") (pintype "bidirectional"))
      (node (ref "CON6") (pin "M$0") (pinfunction "GND_M$0") (pintype "bidirectional"))
      (node (ref "CON6") (pin "M$1") (pinfunction "GND_M$1") (pintype "bidirectional"))
      (node (ref "U$1") (pin "P$2") (pinfunction "P$2_P$2") (pintype "bidirectional"))
    )
    (net (code "10") (name "GPIO1") (class "Default")
      (node (ref "CON2") (pin "1") (pinfunction "1_1") (pintype "passive"))
      (node (ref "D7") (pin "6") (pinfunction "COMMON_6") (pintype "bidirectional"))
      (node (ref "MODULE2") (pin "25") (pinfunction "GPIO1_25") (pintype "bidirectional"))
      (node (ref "PAD7") (pin "P$1") (pinfunction "P$1_P$1") (pintype "bidirectional"))
      (node (ref "R8") (pin "1") (pinfunction "1_1") (pintype "passive"))
    )
    (net (code "11") (name "GPIO2") (class "Default")
      (node (ref "D7") (pin "3") (pinfunction "COMMON_3") (pintype "bidirectional"))
      (node (ref "MODULE2") (pin "24") (pinfunction "GPIO2_24") (pintype "bidirectional"))
      (node (ref "R25") (pin "1") (pinfunction "1_1") (pintype "passive"))
    )
    (net (code "12") (name "Net-(C5-2)") (class "Default")
      (node (ref "C5") (pin "P$2") (pinfunction "2_P$2") (pintype "passive"))
      (node (ref "C7") (pin "P$2") (pinfunction "2_P$2") (pintype "passive"))
      (node (ref "C9") (pin "P$2") (pinfunction "2_P$2") (pintype "passive"))
      (node (ref "CON3") (pin "1") (pinfunction "1_1") (pintype "bidirectional"))
      (node (ref "CON4") (pin "1") (pinfunction "1_1") (pintype "bidirectional"))
      (node (ref "IC1") (pin "4") (pinfunction "OUT_4") (pintype "bidirectional"))
    )
    (net (code "13") (name "Net-(C10-2)") (class "Default")
      (node (ref "C10") (pin "P$2") (pinfunction "2_P$2") (pintype "passive"))
      (node (ref "C6") (pin "P$2") (pinfunction "2_P$2") (pintype "passive"))
      (node (ref "C8") (pin "P$2") (pinfunction "2_P$2") (pintype "passive"))
      (node (ref "CON5") (pin "1") (pinfunction "1_1") (pintype "bidirectional"))
      (node (ref "CON6") (pin "1") (pinfunction "1_1") (pintype "bidirectional"))
      (node (ref "IC2") (pin "4") (pinfunction "OUT_4") (pintype "bidirectional"))
    )
    (net (code "14") (name "Net-(C14-2)") (class "Default")
      (node (ref "C14") (pin "P$2") (pinfunction "2_P$2") (pintype "passive"))
      (node (ref "IC5") (pin "1") (pinfunction "VCC_1") (pintype "bidirectional"))
      (node (ref "R27") (pin "1") (pinfunction "1_1") (pintype "passive"))
    )
    (net (code "15") (name "Net-(CON1-D+)") (class "Default")
      (node (ref "CON1") (pin "3") (pinfunction "D+_3") (pintype "bidirectional"))
      (node (ref "R19") (pin "2") (pinfunction "2_2") (pintype "passive"))
    )
    (net (code "16") (name "Net-(CON1-D-)") (class "Default")
      (node (ref "CON1") (pin "2") (pinfunction "D-_2") (pintype "bidirectional"))
      (node (ref "R20") (pin "2") (pinfunction "2_2") (pintype "passive"))
    )
    (net (code "17") (name "Net-(CON1-VBUS)") (class "Default")
      (node (ref "CON1") (pin "1") (pinfunction "VBUS_1") (pintype "bidirectional"))
      (node (ref "D2") (pin "A") (pinfunction "A_A") (pintype "passive"))
      (node (ref "D4") (pin "4") (pinfunction "A_4") (pintype "bidirectional"))
      (node (ref "R6") (pin "2") (pinfunction "2_2") (pintype "passive"))
    )
    (net (code "18") (name "Net-(CON7-Pad2)") (class "Default")
      (node (ref "CON7") (pin "2") (pinfunction "2_2") (pintype "bidirectional"))
      (node (ref "R8") (pin "2") (pinfunction "2_2") (pintype "passive"))
    )
    (net (code "19") (name "Net-(CON7-Pad3)") (class "Default")
      (node (ref "CON7") (pin "3") (pinfunction "3_3") (pintype "bidirectional"))
      (node (ref "R25") (pin "2") (pinfunction "2_2") (pintype "passive"))
    )
    (net (code "20") (name "Net-(CON8-Pad2)") (class "Default")
      (node (ref "CON8") (pin "2") (pinfunction "2_2") (pintype "passive"))
      (node (ref "R28") (pin "1") (pinfunction "1_1") (pintype "passive"))
    )
    (net (code "21") (name "Net-(CON8-Pad3)") (class "Default")
      (node (ref "CON8") (pin "3") (pinfunction "3_3") (pintype "passive"))
      (node (ref "R29") (pin "1") (pinfunction "1_1") (pintype "passive"))
    )
    (net (code "22") (name "Net-(D4-D1)") (class "Default")
      (node (ref "D4") (pin "2") (pinfunction "D1_2") (pintype "bidirectional"))
      (node (ref "MODULE2") (pin "32") (pinfunction "USB+_32") (pintype "bidirectional"))
      (node (ref "R19") (pin "1") (pinfunction "1_1") (pintype "passive"))
    )
    (net (code "23") (name "Net-(D4-D2)") (class "Default")
      (node (ref "D4") (pin "3") (pinfunction "D2_3") (pintype "bidirectional"))
      (node (ref "MODULE2") (pin "31") (pinfunction "USB-_31") (pintype "bidirectional"))
      (node (ref "R20") (pin "1") (pinfunction "1_1") (pintype "passive"))
    )
    (net (code "24") (name "Net-(F1-1)") (class "Default")
      (node (ref "CON7") (pin "1") (pinfunction "1_1") (pintype "bidirectional"))
      (node (ref "F1") (pin "P$1") (pinfunction "1_P$1") (pintype "passive"))
    )
    (net (code "25") (name "Net-(IC3-CANH)") (class "Default")
      (node (ref "CON3") (pin "2") (pinfunction "2_2") (pintype "bidirectional"))
      (node (ref "CON4") (pin "2") (pinfunction "2_2") (pintype "bidirectional"))
      (node (ref "IC3") (pin "7") (pinfunction "CANH_7") (pintype "bidirectional"))
    )
    (net (code "26") (name "Net-(IC3-CANL)") (class "Default")
      (node (ref "CON3") (pin "3") (pinfunction "3_3") (pintype "bidirectional"))
      (node (ref "CON4") (pin "3") (pinfunction "3_3") (pintype "bidirectional"))
      (node (ref "IC3") (pin "6") (pinfunction "CANL_6") (pintype "bidirectional"))
    )
    (net (code "27") (name "Net-(IC4-CANH)") (class "Default")
      (node (ref "CON5") (pin "2") (pinfunction "2_2") (pintype "bidirectional"))
      (node (ref "CON6") (pin "2") (pinfunction "2_2") (pintype "bidirectional"))
      (node (ref "IC4") (pin "7") (pinfunction "CANH_7") (pintype "bidirectional"))
    )
    (net (code "28") (name "Net-(IC4-CANL)") (class "Default")
      (node (ref "CON5") (pin "3") (pinfunction "3_3") (pintype "bidirectional"))
      (node (ref "CON6") (pin "3") (pinfunction "3_3") (pintype "bidirectional"))
      (node (ref "IC4") (pin "6") (pinfunction "CANL_6") (pintype "bidirectional"))
    )
    (net (code "29") (name "Net-(LED1-PadC)") (class "Default")
      (node (ref "LED1") (pin "C") (pinfunction "C_C") (pintype "bidirectional"))
      (node (ref "R9") (pin "2") (pinfunction "2_2") (pintype "passive"))
    )
    (net (code "30") (name "Net-(LED2-PadC)") (class "Default")
      (node (ref "LED2") (pin "C") (pinfunction "C_C") (pintype "bidirectional"))
      (node (ref "R10") (pin "2") (pinfunction "2_2") (pintype "passive"))
    )
    (net (code "31") (name "Net-(LED3-PadB)") (class "Default")
      (node (ref "LED3") (pin "B") (pinfunction "B_B") (pintype "bidirectional"))
      (node (ref "R11") (pin "1") (pinfunction "1_1") (pintype "passive"))
    )
    (net (code "32") (name "Net-(LED3-PadG)") (class "Default")
      (node (ref "LED3") (pin "G") (pinfunction "G_G") (pintype "bidirectional"))
      (node (ref "R12") (pin "1") (pinfunction "1_1") (pintype "passive"))
    )
    (net (code "33") (name "Net-(LED3-PadR)") (class "Default")
      (node (ref "LED3") (pin "R") (pinfunction "R_R") (pintype "bidirectional"))
      (node (ref "R13") (pin "1") (pinfunction "1_1") (pintype "passive"))
    )
    (net (code "34") (name "Net-(MODULE2-CAN1_LED)") (class "Default")
      (node (ref "MODULE2") (pin "33") (pinfunction "CAN1_LED_33") (pintype "output"))
      (node (ref "R10") (pin "1") (pinfunction "1_1") (pintype "passive"))
    )
    (net (code "35") (name "Net-(MODULE2-CAN2_LED)") (class "Default")
      (node (ref "MODULE2") (pin "34") (pinfunction "CAN2_LED_34") (pintype "output"))
      (node (ref "R9") (pin "1") (pinfunction "1_1") (pintype "passive"))
    )
    (net (code "36") (name "Net-(MODULE2-OVERCURRENT_PROTECT_ADJ)") (class "Default")
      (node (ref "MODULE2") (pin "26") (pinfunction "OVERCURRENT_PROTECT_ADJ_26") (pintype "input"))
      (node (ref "R7") (pin "1") (pinfunction "1_1") (pintype "passive"))
    )
    (net (code "37") (name "Net-(MODULE2-RGB_LED_B)") (class "Default")
      (node (ref "MODULE2") (pin "29") (pinfunction "RGB_LED_B_29") (pintype "output"))
      (node (ref "R11") (pin "2") (pinfunction "2_2") (pintype "passive"))
    )
    (net (code "38") (name "Net-(MODULE2-RGB_LED_G)") (class "Default")
      (node (ref "MODULE2") (pin "28") (pinfunction "RGB_LED_G_28") (pintype "output"))
      (node (ref "R12") (pin "2") (pinfunction "2_2") (pintype "passive"))
    )
    (net (code "39") (name "Net-(MODULE2-RGB_LED_R)") (class "Default")
      (node (ref "MODULE2") (pin "27") (pinfunction "RGB_LED_R_27") (pintype "output"))
      (node (ref "R13") (pin "2") (pinfunction "2_2") (pintype "passive"))
    )
    (net (code "40") (name "Net-(MODULE2-USB_VBUS)") (class "Default")
      (node (ref "MODULE2") (pin "30") (pinfunction "USB_VBUS_30") (pintype "input"))
      (node (ref "R6") (pin "1") (pinfunction "1_1") (pintype "passive"))
    )
    (net (code "41") (name "Net-(Q1-G)") (class "Default")
      (node (ref "Q1") (pin "4G") (pinfunction "G_4G") (pintype "passive"))
      (node (ref "R2") (pin "2") (pinfunction "2_2") (pintype "passive"))
    )
    (net (code "42") (name "Net-(Q2-G)") (class "Default")
      (node (ref "Q2") (pin "4G") (pinfunction "G_4G") (pintype "passive"))
      (node (ref "R3") (pin "2") (pinfunction "2_2") (pintype "passive"))
    )
    (net (code "43") (name "Net-(Q3-G)") (class "Default")
      (node (ref "Q3") (pin "4G") (pinfunction "G_4G") (pintype "passive"))
      (node (ref "R1") (pin "2") (pinfunction "2_2") (pintype "passive"))
    )
    (net (code "44") (name "Net-(Q4-G)") (class "Default")
      (node (ref "Q4") (pin "4G") (pinfunction "G_4G") (pintype "passive"))
      (node (ref "R4") (pin "2") (pinfunction "2_2") (pintype "passive"))
    )
    (net (code "45") (name "Net-(Q5-G)") (class "Default")
      (node (ref "Q5") (pin "4G") (pinfunction "G_4G") (pintype "passive"))
      (node (ref "R15") (pin "2") (pinfunction "2_2") (pintype "passive"))
    )
    (net (code "46") (name "Net-(Q6-G)") (class "Default")
      (node (ref "Q6") (pin "4G") (pinfunction "G_4G") (pintype "passive"))
      (node (ref "R16") (pin "2") (pinfunction "2_2") (pintype "passive"))
    )
    (net (code "47") (name "Net-(Q7-G)") (class "Default")
      (node (ref "Q7") (pin "4G") (pinfunction "G_4G") (pintype "passive"))
      (node (ref "R14") (pin "2") (pinfunction "2_2") (pintype "passive"))
    )
    (net (code "48") (name "Net-(Q8-G)") (class "Default")
      (node (ref "Q8") (pin "4G") (pinfunction "G_4G") (pintype "passive"))
      (node (ref "R17") (pin "2") (pinfunction "2_2") (pintype "passive"))
    )
    (net (code "49") (name "Net-(Q9-G)") (class "Default")
      (node (ref "Q9") (pin "4G") (pinfunction "G_4G") (pintype "passive"))
      (node (ref "R22") (pin "2") (pinfunction "2_2") (pintype "passive"))
    )
    (net (code "50") (name "Net-(Q10-G)") (class "Default")
      (node (ref "Q10") (pin "4G") (pinfunction "G_4G") (pintype "passive"))
      (node (ref "R23") (pin "2") (pinfunction "2_2") (pintype "passive"))
    )
    (net (code "51") (name "Net-(Q11-G)") (class "Default")
      (node (ref "Q11") (pin "4G") (pinfunction "G_4G") (pintype "passive"))
      (node (ref "R21") (pin "2") (pinfunction "2_2") (pintype "passive"))
    )
    (net (code "52") (name "Net-(Q12-G)") (class "Default")
      (node (ref "Q12") (pin "4G") (pinfunction "G_4G") (pintype "passive"))
      (node (ref "R24") (pin "2") (pinfunction "2_2") (pintype "passive"))
    )
    (net (code "53") (name "PGND") (class "Default")
      (node (ref "C1") (pin "-") (pinfunction "-_-") (pintype "passive"))
      (node (ref "C2") (pin "-") (pinfunction "-_-") (pintype "passive"))
      (node (ref "C24") (pin "1") (pinfunction "1_1") (pintype "passive"))
      (node (ref "C31") (pin "1") (pinfunction "1_1") (pintype "passive"))
      (node (ref "C32") (pin "1") (pinfunction "1_1") (pintype "passive"))
      (node (ref "C35") (pin "1") (pinfunction "1_1") (pintype "passive"))
      (node (ref "C58") (pin "1") (pinfunction "1_1") (pintype "passive"))
      (node (ref "C62") (pin "1") (pinfunction "1_1") (pintype "passive"))
      (node (ref "C63") (pin "1") (pinfunction "1_1") (pintype "passive"))
      (node (ref "C64") (pin "1") (pinfunction "1_1") (pintype "passive"))
      (node (ref "C66") (pin "1") (pinfunction "1_1") (pintype "passive"))
      (node (ref "D1") (pin "A") (pinfunction "A_A") (pintype "passive"))
      (node (ref "D5") (pin "A") (pinfunction "A_A") (pintype "passive"))
      (node (ref "D6") (pin "A") (pinfunction "A_A") (pintype "passive"))
      (node (ref "PAD4") (pin "P$1") (pinfunction "P$1_P$1") (pintype "bidirectional"))
      (node (ref "Q10") (pin "1S") (pinfunction "S_1S") (pintype "passive"))
      (node (ref "Q10") (pin "2S") (pinfunction "S_2S") (pintype "passive"))
      (node (ref "Q10") (pin "3S") (pinfunction "S_3S") (pintype "passive"))
      (node (ref "Q12") (pin "1S") (pinfunction "S_1S") (pintype "passive"))
      (node (ref "Q12") (pin "2S") (pinfunction "S_2S") (pintype "passive"))
      (node (ref "Q12") (pin "3S") (pinfunction "S_3S") (pintype "passive"))
      (node (ref "R18") (pin "2") (pinfunction "2_2") (pintype "bidirectional"))
      (node (ref "R18") (pin "22") (pinfunction "2_22") (pintype "bidirectional"))
      (node (ref "R5") (pin "2") (pinfunction "2_2") (pintype "bidirectional"))
      (node (ref "R5") (pin "22") (pinfunction "2_22") (pintype "bidirectional"))
      (node (ref "S1") (pin "SHELL") (pinfunction "SHELLL_SHELL") (pintype "bidirectional"))
      (node (ref "U$3") (pin "P$2") (pinfunction "P$2_P$2") (pintype "bidirectional"))
    )
    (net (code "54") (name "PHASE_A") (class "Default")
      (node (ref "MODULE2") (pin "2") (pinfunction "PHASE_A_2") (pintype "input"))
      (node (ref "PAD2") (pin "P$1") (pinfunction "P$1_P$1") (pintype "bidirectional"))
      (node (ref "Q5") (pin "1S") (pinfunction "S_1S") (pintype "passive"))
      (node (ref "Q5") (pin "2S") (pinfunction "S_2S") (pintype "passive"))
      (node (ref "Q5") (pin "3S") (pinfunction "S_3S") (pintype "passive"))
      (node (ref "Q6") (pin "D") (pinfunction "D_D") (pintype "passive"))
      (node (ref "Q7") (pin "1S") (pinfunction "S_1S") (pintype "passive"))
      (node (ref "Q7") (pin "2S") (pinfunction "S_2S") (pintype "passive"))
      (node (ref "Q7") (pin "3S") (pinfunction "S_3S") (pintype "passive"))
      (node (ref "Q8") (pin "D") (pinfunction "D_D") (pintype "passive"))
    )
    (net (code "55") (name "PHASE_A_CURRENT_SHUNT_N") (class "Default")
      (node (ref "MODULE2") (pin "13") (pinfunction "PHASE_A_CURRENT_SHUNT_N_13") (pintype "input"))
      (node (ref "R18") (pin "S1") (pinfunction "S1_S1") (pintype "bidirectional"))
    )
    (net (code "56") (name "PHASE_A_CURRENT_SHUNT_P") (class "Default")
      (node (ref "MODULE2") (pin "14") (pinfunction "PHASE_A_CURRENT_SHUNT_P_14") (pintype "input"))
      (node (ref "R18") (pin "S2") (pinfunction "S2_S2") (pintype "bidirectional"))
    )
    (net (code "57") (name "PHASE_A_GATE_HIGH") (class "Default")
      (node (ref "MODULE2") (pin "1") (pinfunction "PHASE_A_GATE_HIGH_1") (pintype "output"))
      (node (ref "R14") (pin "1") (pinfunction "1_1") (pintype "passive"))
      (node (ref "R15") (pin "1") (pinfunction "1_1") (pintype "passive"))
    )
    (net (code "58") (name "PHASE_A_GATE_LOW") (class "Default")
      (node (ref "MODULE2") (pin "3") (pinfunction "PHASE_A_GATE_LOW_3") (pintype "output"))
      (node (ref "R16") (pin "1") (pinfunction "1_1") (pintype "passive"))
      (node (ref "R17") (pin "1") (pinfunction "1_1") (pintype "passive"))
    )
    (net (code "59") (name "PHASE_A_GND") (class "Default")
      (node (ref "MODULE2") (pin "4") (pinfunction "PHASE_A_GND_4") (pintype "input"))
      (node (ref "Q6") (pin "1S") (pinfunction "S_1S") (pintype "passive"))
      (node (ref "Q6") (pin "2S") (pinfunction "S_2S") (pintype "passive"))
      (node (ref "Q6") (pin "3S") (pinfunction "S_3S") (pintype "passive"))
      (node (ref "Q8") (pin "1S") (pinfunction "S_1S") (pintype "passive"))
      (node (ref "Q8") (pin "2S") (pinfunction "S_2S") (pintype "passive"))
      (node (ref "Q8") (pin "3S") (pinfunction "S_3S") (pintype "passive"))
      (node (ref "R18") (pin "1") (pinfunction "1_1") (pintype "bidirectional"))
      (node (ref "R18") (pin "11") (pinfunction "1_11") (pintype "bidirectional"))
    )
    (net (code "60") (name "PHASE_B") (class "Default")
      (node (ref "MODULE2") (pin "6") (pinfunction "PHASE_B_6") (pintype "input"))
      (node (ref "PAD1") (pin "P$1") (pinfunction "P$1_P$1") (pintype "bidirectional"))
      (node (ref "Q1") (pin "1S") (pinfunction "S_1S") (pintype "passive"))
      (node (ref "Q1") (pin "2S") (pinfunction "S_2S") (pintype "passive"))
      (node (ref "Q1") (pin "3S") (pinfunction "S_3S") (pintype "passive"))
      (node (ref "Q2") (pin "D") (pinfunction "D_D") (pintype "passive"))
      (node (ref "Q3") (pin "1S") (pinfunction "S_1S") (pintype "passive"))
      (node (ref "Q3") (pin "2S") (pinfunction "S_2S") (pintype "passive"))
      (node (ref "Q3") (pin "3S") (pinfunction "S_3S") (pintype "passive"))
      (node (ref "Q4") (pin "D") (pinfunction "D_D") (pintype "passive"))
    )
    (net (code "61") (name "PHASE_B_CURRENT_SHUNT_N") (class "Default")
      (node (ref "MODULE2") (pin "15") (pinfunction "PHASE_B_CURRENT_SHUNT_N_15") (pintype "input"))
      (node (ref "R5") (pin "S1") (pinfunction "S1_S1") (pintype "bidirectional"))
    )
    (net (code "62") (name "PHASE_B_CURRENT_SHUNT_P") (class "Default")
      (node (ref "MODULE2") (pin "16") (pinfunction "PHASE_B_CURRENT_SHUNT_P_16") (pintype "input"))
      (node (ref "R5") (pin "S2") (pinfunction "S2_S2") (pintype "bidirectional"))
    )
    (net (code "63") (name "PHASE_B_GATE_HIGH") (class "Default")
      (node (ref "MODULE2") (pin "5") (pinfunction "PHASE_B_GATE_HIGH_5") (pintype "output"))
      (node (ref "R1") (pin "1") (pinfunction "1_1") (pintype "passive"))
      (node (ref "R2") (pin "1") (pinfunction "1_1") (pintype "passive"))
    )
    (net (code "64") (name "PHASE_B_GATE_LOW") (class "Default")
      (node (ref "MODULE2") (pin "7") (pinfunction "PHASE_B_GATE_LOW_7") (pintype "output"))
      (node (ref "R3") (pin "1") (pinfunction "1_1") (pintype "passive"))
      (node (ref "R4") (pin "1") (pinfunction "1_1") (pintype "passive"))
    )
    (net (code "65") (name "PHASE_B_GND") (class "Default")
      (node (ref "MODULE2") (pin "8") (pinfunction "PHASE_B_GND_8") (pintype "input"))
      (node (ref "Q2") (pin "1S") (pinfunction "S_1S") (pintype "passive"))
      (node (ref "Q2") (pin "2S") (pinfunction "S_2S") (pintype "passive"))
      (node (ref "Q2") (pin "3S") (pinfunction "S_3S") (pintype "passive"))
      (node (ref "Q4") (pin "1S") (pinfunction "S_1S") (pintype "passive"))
      (node (ref "Q4") (pin "2S") (pinfunction "S_2S") (pintype "passive"))
      (node (ref "Q4") (pin "3S") (pinfunction "S_3S") (pintype "passive"))
      (node (ref "R5") (pin "1") (pinfunction "1_1") (pintype "bidirectional"))
      (node (ref "R5") (pin "11") (pinfunction "1_11") (pintype "bidirectional"))
    )
    (net (code "66") (name "PHASE_C") (class "Default")
      (node (ref "MODULE2") (pin "10") (pinfunction "PHASE_C_10") (pintype "input"))
      (node (ref "PAD3") (pin "P$1") (pinfunction "P$1_P$1") (pintype "bidirectional"))
      (node (ref "Q10") (pin "D") (pinfunction "D_D") (pintype "passive"))
      (node (ref "Q11") (pin "1S") (pinfunction "S_1S") (pintype "passive"))
      (node (ref "Q11") (pin "2S") (pinfunction "S_2S") (pintype "passive"))
      (node (ref "Q11") (pin "3S") (pinfunction "S_3S") (pintype "passive"))
      (node (ref "Q12") (pin "D") (pinfunction "D_D") (pintype "passive"))
      (node (ref "Q9") (pin "1S") (pinfunction "S_1S") (pintype "passive"))
      (node (ref "Q9") (pin "2S") (pinfunction "S_2S") (pintype "passive"))
      (node (ref "Q9") (pin "3S") (pinfunction "S_3S") (pintype "passive"))
    )
    (net (code "67") (name "PHASE_C_GATE_HIGH") (class "Default")
      (node (ref "MODULE2") (pin "9") (pinfunction "PHASE_C_GATE_HIGH_9") (pintype "output"))
      (node (ref "R21") (pin "1") (pinfunction "1_1") (pintype "passive"))
      (node (ref "R22") (pin "1") (pinfunction "1_1") (pintype "passive"))
    )
    (net (code "68") (name "PHASE_C_GATE_LOW") (class "Default")
      (node (ref "MODULE2") (pin "11") (pinfunction "PHASE_C_GATE_LOW_11") (pintype "output"))
      (node (ref "R23") (pin "1") (pinfunction "1_1") (pintype "passive"))
      (node (ref "R24") (pin "1") (pinfunction "1_1") (pintype "passive"))
    )
    (net (code "69") (name "PHASE_C_GND") (class "Default")
      (node (ref "MODULE2") (pin "12") (pinfunction "PHASE_C_GND_12") (pintype "input"))
      (node (ref "S1") (pin "IN") (pinfunction "IN_IN") (pintype "bidirectional"))
    )
    (net (code "70") (name "TEMPERATURE_SENSOR") (class "Default")
      (node (ref "C13") (pin "2") (pinfunction "2_2") (pintype "passive"))
      (node (ref "IC5") (pin "2") (pinfunction "OUT_2") (pintype "bidirectional"))
      (node (ref "MODULE2") (pin "17") (pinfunction "TEMPERATURE_SENSOR_17") (pintype "input"))
    )
    (net (code "71") (name "UART_RX") (class "Default")
      (node (ref "MODULE2") (pin "20") (pinfunction "UART_RX_20") (pintype "input"))
      (node (ref "R29") (pin "2") (pinfunction "2_2") (pintype "passive"))
    )
    (net (code "72") (name "UART_TX") (class "Default")
      (node (ref "MODULE2") (pin "19") (pinfunction "UART_TX_19") (pintype "output"))
      (node (ref "R28") (pin "2") (pinfunction "2_2") (pintype "passive"))
    )
    (net (code "73") (name "VDC") (class "Default")
      (node (ref "C1") (pin "+") (pinfunction "+_+") (pintype "passive"))
      (node (ref "C2") (pin "+") (pinfunction "+_+") (pintype "passive"))
      (node (ref "C24") (pin "2") (pinfunction "2_2") (pintype "passive"))
      (node (ref "C31") (pin "2") (pinfunction "2_2") (pintype "passive"))
      (node (ref "C32") (pin "2") (pinfunction "2_2") (pintype "passive"))
      (node (ref "C35") (pin "2") (pinfunction "2_2") (pintype "passive"))
      (node (ref "C58") (pin "2") (pinfunction "2_2") (pintype "passive"))
      (node (ref "C62") (pin "2") (pinfunction "2_2") (pintype "passive"))
      (node (ref "C63") (pin "2") (pinfunction "2_2") (pintype "passive"))
      (node (ref "C64") (pin "2") (pinfunction "2_2") (pintype "passive"))
      (node (ref "C66") (pin "2") (pinfunction "2_2") (pintype "passive"))
      (node (ref "D1") (pin "C") (pinfunction "C_C") (pintype "passive"))
      (node (ref "D5") (pin "C") (pinfunction "C_C") (pintype "passive"))
      (node (ref "D6") (pin "C") (pinfunction "C_C") (pintype "passive"))
      (node (ref "MODULE2") (pin "42") (pinfunction "VDC_42") (pintype "power_in"))
      (node (ref "PAD5") (pin "P$1") (pinfunction "P$1_P$1") (pintype "bidirectional"))
      (node (ref "Q1") (pin "D") (pinfunction "D_D") (pintype "passive"))
      (node (ref "Q11") (pin "D") (pinfunction "D_D") (pintype "passive"))
      (node (ref "Q3") (pin "D") (pinfunction "D_D") (pintype "passive"))
      (node (ref "Q5") (pin "D") (pinfunction "D_D") (pintype "passive"))
      (node (ref "Q7") (pin "D") (pinfunction "D_D") (pintype "passive"))
      (node (ref "Q9") (pin "D") (pinfunction "D_D") (pintype "passive"))
    )
    (net (code "74") (name "VDD_5V") (class "Default")
      (node (ref "C11") (pin "1") (pinfunction "1_1") (pintype "passive"))
      (node (ref "C12") (pin "1") (pinfunction "1_1") (pintype "passive"))
      (node (ref "C3") (pin "1") (pinfunction "1_1") (pintype "passive"))
      (node (ref "C4") (pin "1") (pinfunction "1_1") (pintype "passive"))
      (node (ref "C45") (pin "1") (pinfunction "1_1") (pintype "passive"))
      (node (ref "CON8") (pin "1") (pinfunction "1_1") (pintype "passive"))
      (node (ref "D2") (pin "C") (pinfunction "C_C") (pintype "passive"))
      (node (ref "D7") (pin "2") (pinfunction "C_2") (pintype "passive"))
      (node (ref "D7") (pin "5") (pinfunction "C_5") (pintype "passive"))
      (node (ref "F1") (pin "P$2") (pinfunction "2_P$2") (pintype "passive"))
      (node (ref "IC1") (pin "3") (pinfunction "IN_3") (pintype "bidirectional"))
      (node (ref "IC2") (pin "3") (pinfunction "IN_3") (pintype "bidirectional"))
      (node (ref "IC3") (pin "3") (pinfunction "VCC_3") (pintype "bidirectional"))
      (node (ref "IC3") (pin "5") (pinfunction "VIO_5") (pintype "bidirectional"))
      (node (ref "IC4") (pin "3") (pinfunction "VCC_3") (pintype "bidirectional"))
      (node (ref "IC4") (pin "5") (pinfunction "VIO_5") (pintype "bidirectional"))
      (node (ref "LED1") (pin "A") (pinfunction "A_A") (pintype "bidirectional"))
      (node (ref "LED2") (pin "A") (pinfunction "A_A") (pintype "bidirectional"))
      (node (ref "LED3") (pin "+") (pinfunction "A_+") (pintype "bidirectional"))
      (node (ref "LED5") (pin "A") (pinfunction "A_A") (pintype "bidirectional"))
      (node (ref "MODULE2") (pin "40") (pinfunction "5V_OUT_40") (pintype "power_in"))
      (node (ref "R27") (pin "2") (pinfunction "2_2") (pintype "passive"))
    )
    (net (code "75") (name "unconnected-(CON8-Pad4)") (class "Default")
      (node (ref "CON8") (pin "4") (pinfunction "4_4") (pintype "passive"))
    )
    (net (code "76") (name "unconnected-(CON8-Pad5)") (class "Default")
      (node (ref "CON8") (pin "5") (pinfunction "5_5") (pintype "passive"))
    )
    (net (code "77") (name "unconnected-(IC1-D1-Pad5)") (class "Default")
      (node (ref "IC1") (pin "5") (pinfunction "D1_5") (pintype "bidirectional"))
    )
    (net (code "78") (name "unconnected-(IC1-D2-Pad6)") (class "Default")
      (node (ref "IC1") (pin "6") (pinfunction "D2_6") (pintype "bidirectional"))
    )
    (net (code "79") (name "unconnected-(IC2-D1-Pad5)") (class "Default")
      (node (ref "IC2") (pin "5") (pinfunction "D1_5") (pintype "bidirectional"))
    )
    (net (code "80") (name "unconnected-(IC2-D2-Pad6)") (class "Default")
      (node (ref "IC2") (pin "6") (pinfunction "D2_6") (pintype "bidirectional"))
    )
    (net (code "81") (name "unconnected-(MODULE2-NC-Pad35)") (class "Default")
      (node (ref "MODULE2") (pin "35") (pinfunction "NC_35") (pintype "no_connect"))
    )
    (net (code "82") (name "unconnected-(MODULE2-POWER_ENABLE_IN-Pad18)") (class "Default")
      (node (ref "MODULE2") (pin "18") (pinfunction "POWER_ENABLE_IN_18") (pintype "input"))
    )
  )
)
